# XYZ_Magnitometer.net
KiCad netlist of a schematic drawn in EAGLE
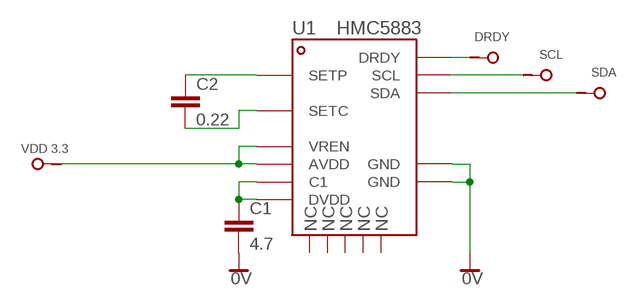
[diagram p0: schematic, sheet 1]

(export (version "E")
  (design (tool "Eeschema 10.0.6"))
  (components
    (comp (ref "C1")
      (value "4.7")
      (footprint "eagle-import:C1206K")
      (libsource (lib "eagle-import") (part "SMD_CAPC1206K"))
    )
    (comp (ref "C2")
      (value "0.22")
      (footprint "eagle-import:C0805K")
      (libsource (lib "eagle-import") (part "SMD_CAPC0805K"))
    )
    (comp (ref "P1")
      (value "SDA")
      (footprint "eagle-import:1_PIN_PLANAR")
      (libsource (lib "eagle-import") (part "1_PIN_CONPLANAR"))
    )
    (comp (ref "P2")
      (value "VDD 3.3")
      (footprint "eagle-import:1_PIN_PLANAR")
      (libsource (lib "eagle-import") (part "1_PIN_CONPLANAR"))
    )
    (comp (ref "P3")
      (value "SCL")
      (footprint "eagle-import:1_PIN_PLANAR")
      (libsource (lib "eagle-import") (part "1_PIN_CONPLANAR"))
    )
    (comp (ref "P5")
      (value "DRDY")
      (footprint "eagle-import:1_PIN_PLANAR")
      (libsource (lib "eagle-import") (part "1_PIN_CONPLANAR"))
    )
    (comp (ref "U1")
      (value "HMC5883")
      (footprint "eagle-import:QFN16-4X4")
      (libsource (lib "eagle-import") (part "HMC5883"))
    )
  )
  (nets
    (net (code "1") (name "/1") (class "Default")
      (node (ref "U1") (pin "P$3") (pinfunction "1_P$3") (pintype "power_in"))
    )
    (net (code "2") (name "/2") (class "Default")
      (node (ref "U1") (pin "P$4") (pinfunction "2_P$4") (pintype "power_in"))
    )
    (net (code "3") (name "/3") (class "Default")
      (node (ref "U1") (pin "P$5") (pinfunction "3_P$5") (pintype "power_in"))
    )
    (net (code "4") (name "/4") (class "Default")
      (node (ref "U1") (pin "P$6") (pinfunction "4_P$6") (pintype "power_in"))
    )
    (net (code "5") (name "/5") (class "Default")
      (node (ref "U1") (pin "P$7") (pinfunction "5_P$7") (pintype "power_in"))
    )
    (net (code "6") (name "0V") (class "Default")
      (node (ref "C1") (pin "2") (pinfunction "2_2") (pintype "passive"))
      (node (ref "U1") (pin "P$11") (pinfunction "GND_P$11") (pintype "power_in"))
      (node (ref "U1") (pin "P$9") (pinfunction "GND_P$9") (pintype "power_in"))
    )
    (net (code "7") (name "Net-(U1-AVDD)") (class "Default")
      (node (ref "P2") (pin "P$1") (pinfunction "P$1_P$1") (pintype "bidirectional"))
      (node (ref "U1") (pin "P$14") (pinfunction "VREN_P$14") (pintype "bidirectional"))
      (node (ref "U1") (pin "P$2") (pinfunction "AVDD_P$2") (pintype "power_in"))
    )
    (net (code "8") (name "Net-(U1-C1)") (class "Default")
      (node (ref "C1") (pin "1") (pinfunction "1_1") (pintype "passive"))
      (node (ref "U1") (pin "P$10") (pinfunction "C1_P$10") (pintype "bidirectional"))
      (node (ref "U1") (pin "P$13") (pinfunction "DVDD_P$13") (pintype "power_in"))
    )
    (net (code "9") (name "Net-(U1-DRDY)") (class "Default")
      (node (ref "P5") (pin "P$1") (pinfunction "P$1_P$1") (pintype "bidirectional"))
      (node (ref "U1") (pin "P$15") (pinfunction "DRDY_P$15") (pintype "bidirectional"))
    )
    (net (code "10") (name "Net-(U1-SCL)") (class "Default")
      (node (ref "P3") (pin "P$1") (pinfunction "P$1_P$1") (pintype "bidirectional"))
      (node (ref "U1") (pin "P$1") (pinfunction "SCL_P$1") (pintype "bidirectional"))
    )
    (net (code "11") (name "Net-(U1-SDA)") (class "Default")
      (node (ref "P1") (pin "P$1") (pinfunction "P$1_P$1") (pintype "bidirectional"))
      (node (ref "U1") (pin "P$16") (pinfunction "SDA_P$16") (pintype "bidirectional"))
    )
    (net (code "12") (name "Net-(U1-SETC)") (class "Default")
      (node (ref "C2") (pin "2") (pinfunction "2_2") (pintype "passive"))
      (node (ref "U1") (pin "P$12") (pinfunction "SETC_P$12") (pintype "bidirectional"))
    )
    (net (code "13") (name "Net-(U1-SETP)") (class "Default")
      (node (ref "C2") (pin "1") (pinfunction "1_1") (pintype "passive"))
      (node (ref "U1") (pin "P$8") (pinfunction "SETP_P$8") (pintype "bidirectional"))
    )
  )
)
